# SCH.net
KiCad netlist of a schematic drawn in Altium Designer
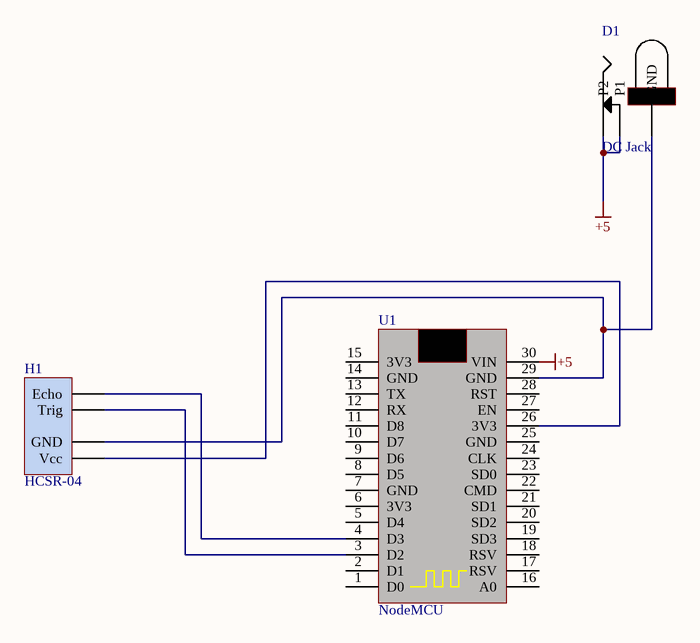
[diagram p0: SCH.SchDoc]

(export (version "E")
  (design (tool "Eeschema 10.0.6"))
  (components
    (comp (ref "D1") (value "DC Jack") (footprint "DC Jack") (libsource (lib "Schlib") (part "DC Jack")))
    (comp (ref "H1") (value "HCSR-04") (footprint "HCSR-04") (libsource (lib "Schlib") (part "HCSR-04")))
    (comp (ref "U1") (value "NodeMCU") (footprint "ESP8266") (libsource (lib "Schlib") (part "NodeMCU")))
  )
  (nets
    (net (code "1") (name "+5") (class "Default")
      (node (ref "D1") (pin "2") (pinfunction "P2_2") (pintype "passive"))
      (node (ref "D1") (pin "3") (pinfunction "P1_3") (pintype "passive"))
      (node (ref "U1") (pin "30") (pinfunction "VIN_30") (pintype "passive"))
    )
    (net (code "2") (name "Net-(D1-GND)") (class "Default")
      (node (ref "D1") (pin "1") (pinfunction "GND_1") (pintype "passive"))
      (node (ref "H1") (pin "1") (pinfunction "GND_1") (pintype "passive"))
      (node (ref "U1") (pin "29") (pinfunction "GND_29") (pintype "passive"))
    )
    (net (code "3") (name "Net-(H1-Echo)") (class "Default")
      (node (ref "H1") (pin "2") (pinfunction "Echo_2") (pintype "passive"))
      (node (ref "U1") (pin "4") (pinfunction "D3_4") (pintype "passive"))
    )
    (net (code "4") (name "Net-(H1-Trig)") (class "Default")
      (node (ref "H1") (pin "3") (pinfunction "Trig_3") (pintype "passive"))
      (node (ref "U1") (pin "3") (pinfunction "D2_3") (pintype "passive"))
    )
    (net (code "5") (name "Net-(H1-Vcc)") (class "Default")
      (node (ref "H1") (pin "4") (pinfunction "Vcc_4") (pintype "passive"))
      (node (ref "U1") (pin "26") (pinfunction "3V3_26") (pintype "passive"))
    )
    (net (code "6") (name "unconnected-(U1-3V3-Pad6)") (class "Default")
      (node (ref "U1") (pin "6") (pinfunction "3V3_6") (pintype "passive"))
    )
    (net (code "7") (name "unconnected-(U1-3V3-Pad15)") (class "Default")
      (node (ref "U1") (pin "15") (pinfunction "3V3_15") (pintype "passive"))
    )
    (net (code "8") (name "unconnected-(U1-A0-Pad16)") (class "Default")
      (node (ref "U1") (pin "16") (pinfunction "A0_16") (pintype "passive"))
    )
    (net (code "9") (name "unconnected-(U1-CLK-Pad24)") (class "Default")
      (node (ref "U1") (pin "24") (pinfunction "CLK_24") (pintype "passive"))
    )
    (net (code "10") (name "unconnected-(U1-CMD-Pad22)") (class "Default")
      (node (ref "U1") (pin "22") (pinfunction "CMD_22") (pintype "passive"))
    )
    (net (code "11") (name "unconnected-(U1-D0-Pad1)") (class "Default")
      (node (ref "U1") (pin "1") (pinfunction "D0_1") (pintype "passive"))
    )
    (net (code "12") (name "unconnected-(U1-D1-Pad2)") (class "Default")
      (node (ref "U1") (pin "2") (pinfunction "D1_2") (pintype "passive"))
    )
    (net (code "13") (name "unconnected-(U1-D4-Pad5)") (class "Default")
      (node (ref "U1") (pin "5") (pinfunction "D4_5") (pintype "passive"))
    )
    (net (code "14") (name "unconnected-(U1-D5-Pad8)") (class "Default")
      (node (ref "U1") (pin "8") (pinfunction "D5_8") (pintype "passive"))
    )
    (net (code "15") (name "unconnected-(U1-D6-Pad9)") (class "Default")
      (node (ref "U1") (pin "9") (pinfunction "D6_9") (pintype "passive"))
    )
    (net (code "16") (name "unconnected-(U1-D7-Pad10)") (class "Default")
      (node (ref "U1") (pin "10") (pinfunction "D7_10") (pintype "passive"))
    )
    (net (code "17") (name "unconnected-(U1-D8-Pad11)") (class "Default")
      (node (ref "U1") (pin "11") (pinfunction "D8_11") (pintype "passive"))
    )
    (net (code "18") (name "unconnected-(U1-EN-Pad27)") (class "Default")
      (node (ref "U1") (pin "27") (pinfunction "EN_27") (pintype "passive"))
    )
    (net (code "19") (name "unconnected-(U1-GND-Pad7)") (class "Default")
      (node (ref "U1") (pin "7") (pinfunction "GND_7") (pintype "passive"))
    )
    (net (code "20") (name "unconnected-(U1-GND-Pad14)") (class "Default")
      (node (ref "U1") (pin "14") (pinfunction "GND_14") (pintype "passive"))
    )
    (net (code "21") (name "unconnected-(U1-GND-Pad25)") (class "Default")
      (node (ref "U1") (pin "25") (pinfunction "GND_25") (pintype "passive"))
    )
    (net (code "22") (name "unconnected-(U1-RST-Pad28)") (class "Default")
      (node (ref "U1") (pin "28") (pinfunction "RST_28") (pintype "passive"))
    )
    (net (code "23") (name "unconnected-(U1-RSV-Pad17)") (class "Default")
      (node (ref "U1") (pin "17") (pinfunction "RSV_17") (pintype "passive"))
    )
    (net (code "24") (name "unconnected-(U1-RSV-Pad18)") (class "Default")
      (node (ref "U1") (pin "18") (pinfunction "RSV_18") (pintype "passive"))
    )
    (net (code "25") (name "unconnected-(U1-RX-Pad12)") (class "Default")
      (node (ref "U1") (pin "12") (pinfunction "RX_12") (pintype "passive"))
    )
    (net (code "26") (name "unconnected-(U1-SD0-Pad23)") (class "Default")
      (node (ref "U1") (pin "23") (pinfunction "SD0_23") (pintype "passive"))
    )
    (net (code "27") (name "unconnected-(U1-SD1-Pad21)") (class "Default")
      (node (ref "U1") (pin "21") (pinfunction "SD1_21") (pintype "passive"))
    )
    (net (code "28") (name "unconnected-(U1-SD2-Pad20)") (class "Default")
      (node (ref "U1") (pin "20") (pinfunction "SD2_20") (pintype "passive"))
    )
    (net (code "29") (name "unconnected-(U1-SD3-Pad19)") (class "Default")
      (node (ref "U1") (pin "19") (pinfunction "SD3_19") (pintype "passive"))
    )
    (net (code "30") (name "unconnected-(U1-TX-Pad13)") (class "Default")
      (node (ref "U1") (pin "13") (pinfunction "TX_13") (pintype "passive"))
    )
  )
)
